# BluetoothAdapter2_0.net
KiCad netlist of a schematic drawn in Altium Designer
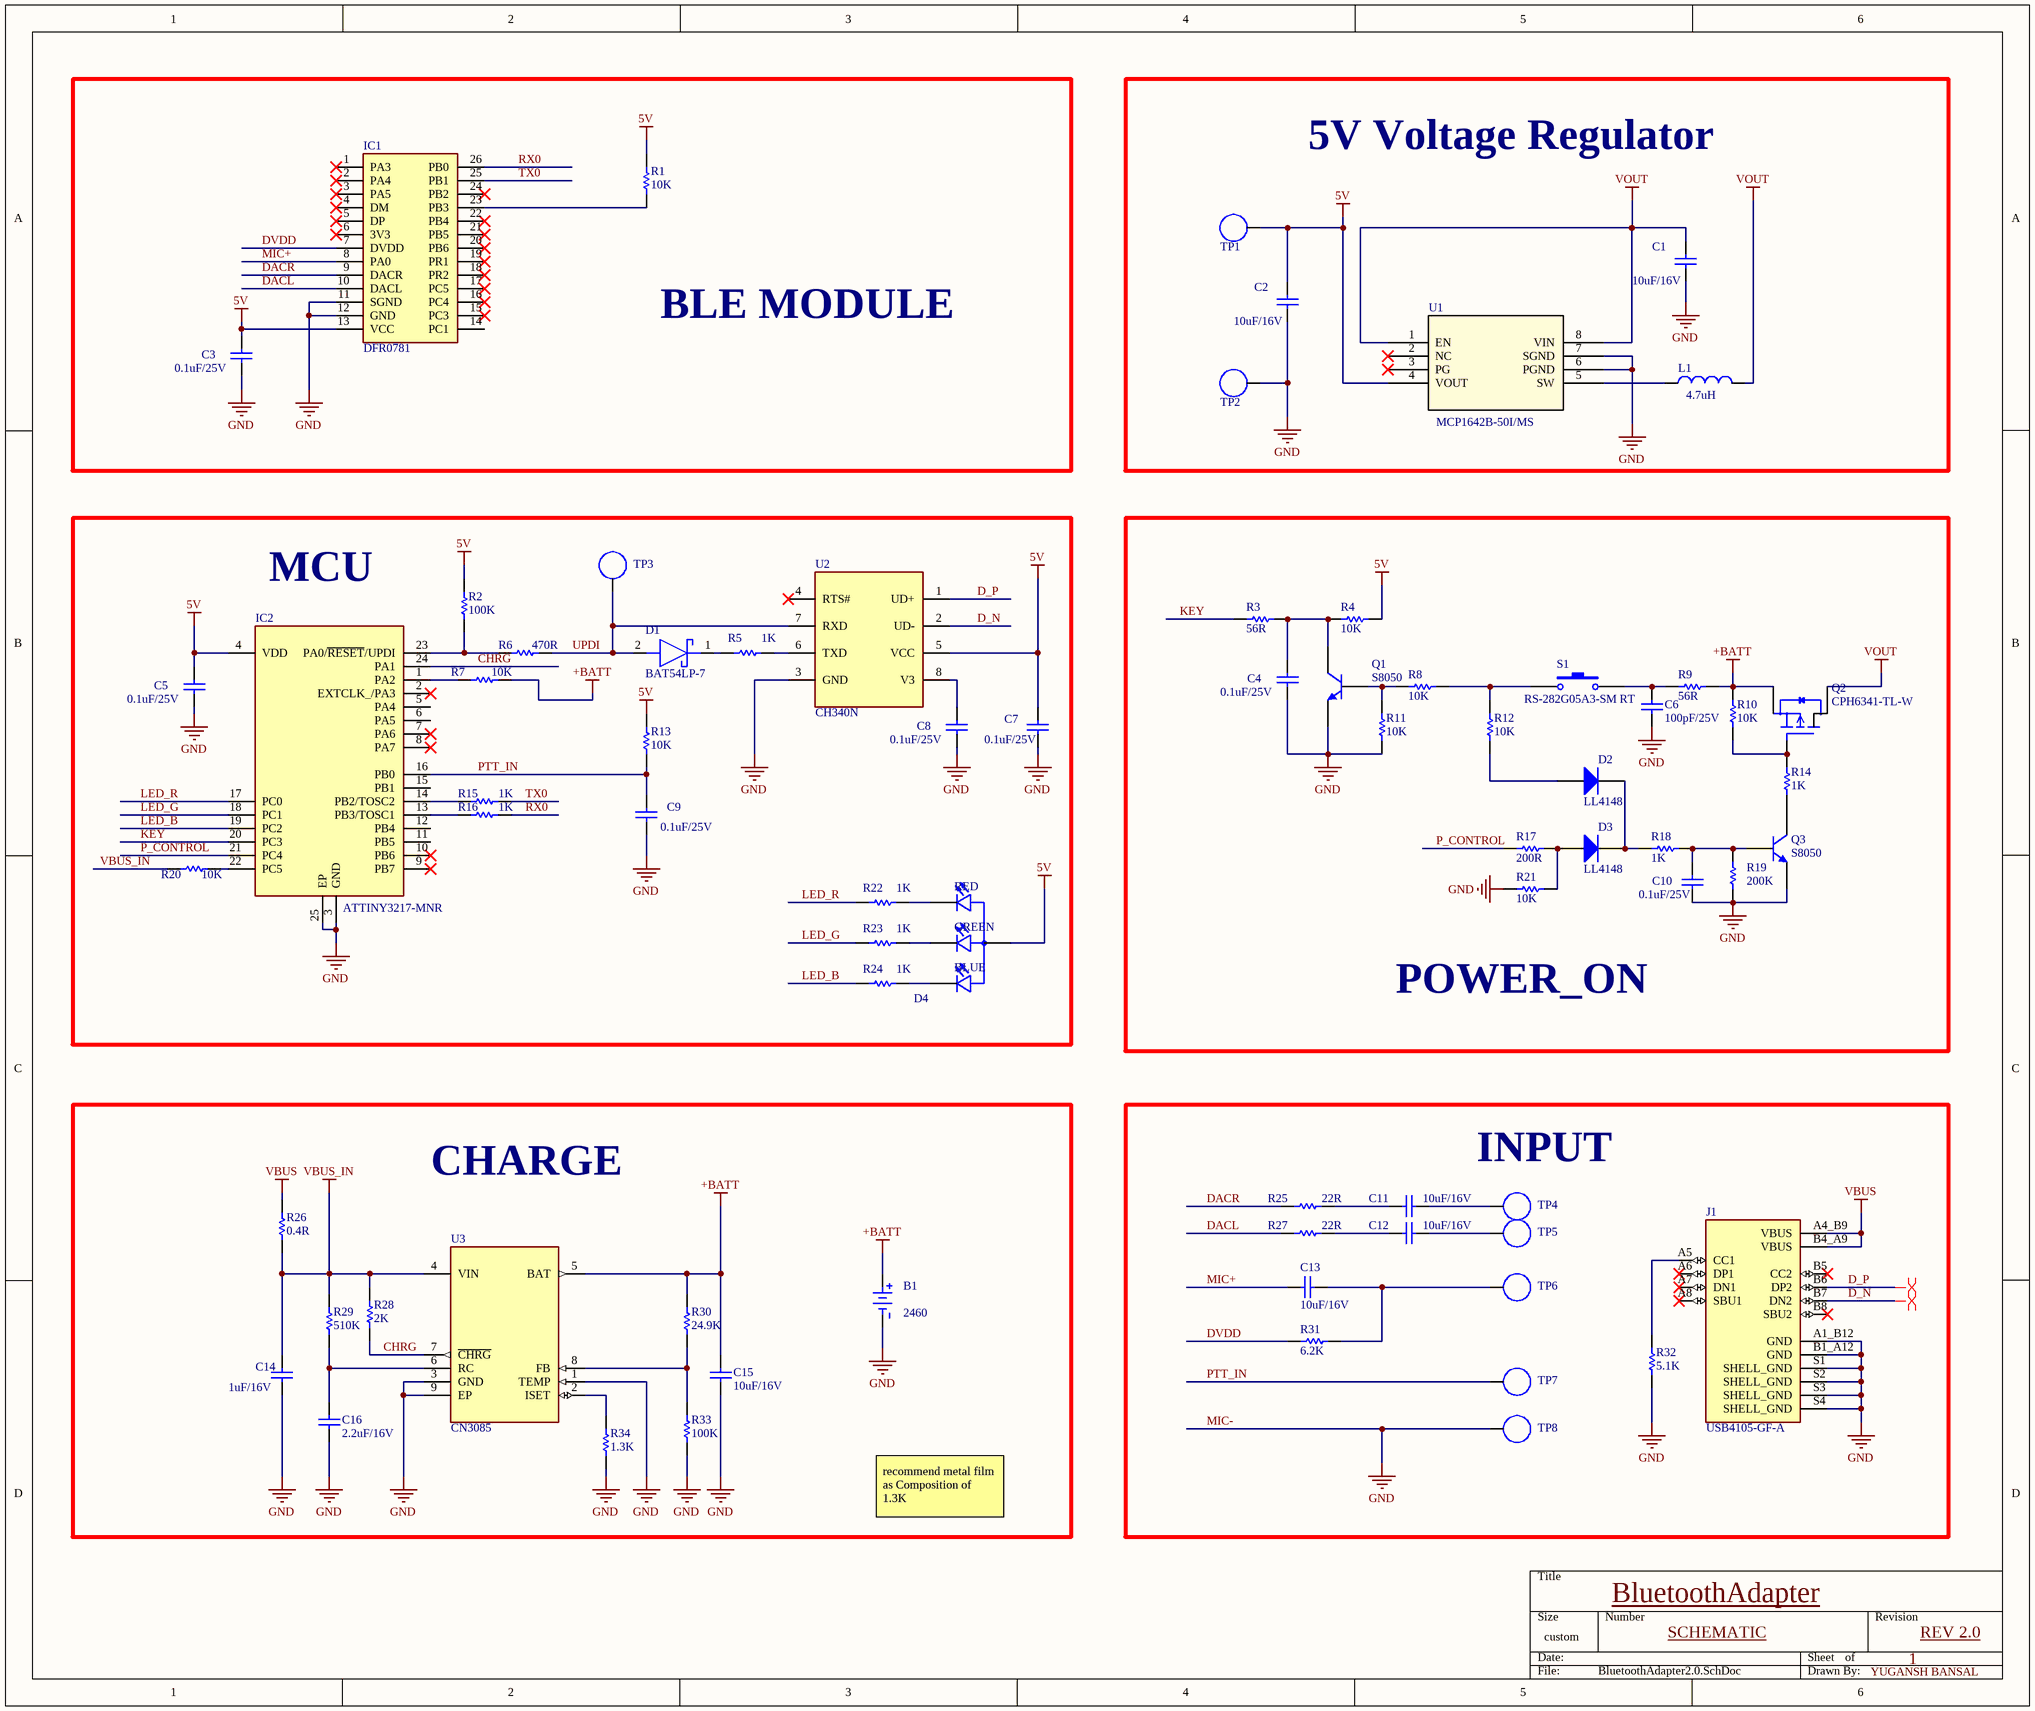
[diagram p0: BluetoothAdapter2.0.SchDoc]

(export (version "E")
  (design (tool "Eeschema 10.0.6"))
  (components
    (comp (ref "B1")
      (value "2460")
      (footprint "BluetoothAdapter:2460_KEY")
      (description "Battery Holder (Open) AA 1 Cell PC Pin")
      (fields
        (field (name "MANUFACTURER") "Keystone Electronics")
        (field (name "DIGI-KEY PART NUMBER") "36-2460-ND")
      )
      (libsource (lib "BluetoothAdapter") (part "2460"))
    )
    (comp (ref "C1")
      (value "10uF/16V")
      (footprint "BluetoothAdapter:C0603S")
      (description "10 µF ±20% 16V Ceramic Capacitor X5R 0603 (1608 Metric)")
      (fields
        (field (name "MANUFACTURER") "Murata Electronics")
        (field (name "DIGI-KEY PART NUMBER") "490-10729-6-ND")
      )
      (libsource (lib "myLib") (part "Cap"))
    )
    (comp (ref "C2")
      (value "10uF/16V")
      (footprint "BluetoothAdapter:C0603S")
      (description "10 µF ±20% 16V Ceramic Capacitor X5R 0603 (1608 Metric)")
      (fields
        (field (name "MANUFACTURER") "Murata Electronics")
        (field (name "DIGI-KEY PART NUMBER") "490-10729-6-ND")
      )
      (libsource (lib "myLib") (part "Cap"))
    )
    (comp (ref "C3")
      (value "0.1uF/25V")
      (footprint "BluetoothAdapter:C0603S")
      (description "0.1 µF ±10% 25V Ceramic Capacitor X7R 0603 (1608 Metric)")
      (fields
        (field (name "MANUFACTURER") "KEMET")
        (field (name "DIGI-KEY PART NUMBER") "399-C0603C104K3RAC7867TR-ND")
      )
      (libsource (lib "myLib") (part "Cap"))
    )
    (comp (ref "C4")
      (value "0.1uF/25V")
      (footprint "BluetoothAdapter:C0603S")
      (description "0.1 µF ±10% 25V Ceramic Capacitor X7R 0603 (1608 Metric)")
      (fields
        (field (name "MANUFACTURER") "KEMET")
        (field (name "DIGI-KEY PART NUMBER") "399-C0603C104K3RAC7867TR-ND")
      )
      (libsource (lib "myLib") (part "Cap"))
    )
    (comp (ref "C5")
      (value "0.1uF/25V")
      (footprint "BluetoothAdapter:C0603S")
      (description "0.1 µF ±10% 25V Ceramic Capacitor X7R 0603 (1608 Metric)")
      (fields
        (field (name "MANUFACTURER") "KEMET")
        (field (name "DIGI-KEY PART NUMBER") "399-C0603C104K3RAC7867TR-ND")
      )
      (libsource (lib "myLib") (part "Cap"))
    )
    (comp (ref "C6")
      (value "100pF/25V")
      (footprint "BluetoothAdapter:C0603S")
      (description "0.1 µF ±10% 25V Ceramic Capacitor X7R 0603 (1608 Metric)")
      (fields
        (field (name "MANUFACTURER") "KEMET")
        (field (name "DIGI-KEY PART NUMBER") "399-C0603C101K3RACAUTODKR-ND")
      )
      (libsource (lib "myLib") (part "Cap"))
    )
    (comp (ref "C7")
      (value "0.1uF/25V")
      (footprint "BluetoothAdapter:C0603S")
      (description "0.1 µF ±10% 25V Ceramic Capacitor X7R 0603 (1608 Metric)")
      (fields
        (field (name "MANUFACTURER") "KEMET")
        (field (name "DIGI-KEY PART NUMBER") "399-C0603C104K3RAC7867TR-ND")
      )
      (libsource (lib "myLib") (part "Cap"))
    )
    (comp (ref "C8")
      (value "0.1uF/25V")
      (footprint "BluetoothAdapter:C0603S")
      (description "0.1 µF ±10% 25V Ceramic Capacitor X7R 0603 (1608 Metric)")
      (fields
        (field (name "MANUFACTURER") "KEMET")
        (field (name "DIGI-KEY PART NUMBER") "399-C0603C104K3RAC7867TR-ND")
      )
      (libsource (lib "myLib") (part "Cap"))
    )
    (comp (ref "C9")
      (value "0.1uF/25V")
      (footprint "BluetoothAdapter:C0603S")
      (description "0.1 µF ±10% 25V Ceramic Capacitor X7R 0603 (1608 Metric)")
      (fields
        (field (name "MANUFACTURER") "KEMET")
        (field (name "DIGI-KEY PART NUMBER") "399-C0603C104K3RAC7867TR-ND")
      )
      (libsource (lib "myLib") (part "Cap"))
    )
    (comp (ref "C10")
      (value "0.1uF/25V")
      (footprint "BluetoothAdapter:C0603S")
      (description "0.1 µF ±10% 25V Ceramic Capacitor X7R 0603 (1608 Metric)")
      (fields
        (field (name "MANUFACTURER") "KEMET")
        (field (name "DIGI-KEY PART NUMBER") "399-C0603C104K3RAC7867TR-ND")
      )
      (libsource (lib "myLib") (part "Cap"))
    )
    (comp (ref "C11")
      (value "10uF/16V")
      (footprint "BluetoothAdapter:C0603S")
      (description "10 µF ±20% 16V Ceramic Capacitor X5R 0603 (1608 Metric)")
      (fields
        (field (name "MANUFACTURER") "Murata Electronics")
        (field (name "DIGI-KEY PART NUMBER") "490-10729-6-ND")
      )
      (libsource (lib "myLib") (part "Cap"))
    )
    (comp (ref "C12")
      (value "10uF/16V")
      (footprint "BluetoothAdapter:C0603S")
      (description "10 µF ±20% 16V Ceramic Capacitor X5R 0603 (1608 Metric)")
      (fields
        (field (name "MANUFACTURER") "Murata Electronics")
        (field (name "DIGI-KEY PART NUMBER") "490-10729-6-ND")
      )
      (libsource (lib "myLib") (part "Cap"))
    )
    (comp (ref "C13")
      (value "10uF/16V")
      (footprint "BluetoothAdapter:C0603S")
      (description "10 µF ±20% 16V Ceramic Capacitor X5R 0603 (1608 Metric)")
      (fields
        (field (name "MANUFACTURER") "Murata Electronics")
        (field (name "DIGI-KEY PART NUMBER") "490-10729-6-ND")
      )
      (libsource (lib "myLib") (part "Cap"))
    )
    (comp (ref "C14")
      (value "1uF/16V")
      (footprint "BluetoothAdapter:C0603S")
      (description "1 µF ±10% 16V Ceramic Capacitor X7R 0603 (1608 Metric)")
      (fields (field (name "MANUFACTURER") "YAGEO") (field (name "DIGI-KEY PART NUMBER") "311-1446-6-ND"))
      (libsource (lib "myLib") (part "Cap"))
    )
    (comp (ref "C15")
      (value "10uF/16V")
      (footprint "BluetoothAdapter:C0603S")
      (description "10 µF ±20% 16V Ceramic Capacitor X5R 0603 (1608 Metric)")
      (fields
        (field (name "MANUFACTURER") "Murata Electronics")
        (field (name "DIGI-KEY PART NUMBER") "490-10729-6-ND")
      )
      (libsource (lib "myLib") (part "Cap"))
    )
    (comp (ref "C16")
      (value "2.2uF/16V")
      (footprint "BluetoothAdapter:C0603S")
      (description "2.2 µF ±10% 16V Ceramic Capacitor X7R 0603 (1608 Metric)")
      (fields
        (field (name "MANUFACTURER") "Murata Electronics")
        (field (name "DIGI-KEY PART NUMBER") "490-GRM188Z71C225KE43DDKR-ND")
      )
      (libsource (lib "myLib") (part "Cap"))
    )
    (comp (ref "D1")
      (value "BAT54LP-7")
      (footprint "BluetoothAdapter:DESD3V3S1BL7B")
      (description "Diode 30 V 200mA Surface Mount X1-DFN1006-2")
      (fields
        (field (name "MANUFACTURER") "Diodes Inc.")
        (field (name "DIGI-KEY PART NUMBER") "BAT54LPDIDKR-ND")
      )
      (libsource (lib "BluetoothAdapter") (part "BAT54LP-7"))
    )
    (comp (ref "D2")
      (value "LL4148")
      (footprint "DIO_LL4148")
      (description "Diode Standard 100 V 200mA Surface Mount SOD-80")
      (fields (field (name "MANUFACTURER") "onsemi") (field (name "DIGI-KEY PART NUMBER") "LL4148FSCT-ND"))
      (libsource (lib "Miscellaneous Devices") (part "Diode"))
    )
    (comp (ref "D3")
      (value "LL4148")
      (footprint "DIO_LL4148")
      (description "Diode Standard 100 V 200mA Surface Mount SOD-80")
      (fields (field (name "MANUFACTURER") "onsemi") (field (name "DIGI-KEY PART NUMBER") "LL4148FSCT-ND"))
      (libsource (lib "Miscellaneous Devices") (part "Diode"))
    )
    (comp (ref "D4")
      (value "LED RGB MIXED WHITE ( 1.6(L)X1.6")
      (footprint "BluetoothAdapter:LED_B38G3RGB-10D0003H2U1930")
      (description "Red, Green, Blue (RGB) LED Indication - Discrete 2V Red, 3V Green, 3V Blue 0606 (1616 Metric)")
      (fields
        (field (name "MANUFACTURER") "Harvatek Corporation")
        (field (name "DIGI-KEY PART NUMBER") "3147-B38G3RGB-10D0003H2U1930DKR-ND")
      )
      (libsource (lib "BluetoothAdapter") (part "B38G3RGB-10D0003H2U1930"))
    )
    (comp (ref "IC1")
      (value "DFR0781")
      (footprint "BluetoothAdapter:DFR0781")
      (description "Bluetooth Bluetooth v5.0 Transceiver Module Antenna Not Included Surface Mount")
      (fields (field (name "MANUFACTURER") "DFRobot") (field (name "DIGI-KEY PART NUMBER") "1738-DFR0781-ND"))
      (libsource (lib "BluetoothAdapter") (part "DFR0781"))
    )
    (comp (ref "IC2")
      (value "ATTINY3217-MNR")
      (footprint "BluetoothAdapter:QFN50P400X400X90-25N-D")
      (fields
        (field (name "MANUFACTURER") "Microchip")
        (field (name "DIGI-KEY PART NUMBER") "ATTINY3217-MNRDKR-ND")
        (field (name "Comment") "IC MCU 8BIT 32KB FLASH 24VQFN")
      )
      (libsource (lib "BluetoothAdapter") (part "ATTINY3217-MNR"))
    )
    (comp (ref "J1")
      (value "USB4105-GF-A")
      (footprint "BluetoothAdapter:GCT_USB4105-GF-A")
      (fields
        (field (name "MANUFACTURER") "GCT")
        (field (name "DIGI-KEY PART NUMBER") "2073-USB4105-GF-ADKR-ND")
        (field (name "Comment") "CONN RCP USB2.0 TYP C 24P SMD RA")
      )
      (libsource (lib "BluetoothAdapter") (part "USB4105-GF-A"))
    )
    (comp (ref "L1")
      (value "4.7uH")
      (footprint "BluetoothAdapter:INDC2520X100N")
      (description "4.7 µH Shielded Multilayer Inductor 1.3 A 120mOhm 1008 (2520 Metric)")
      (fields
        (field (name "MANUFACTURER") "Abracon LLC")
        (field (name "DIGI-KEY PART NUMBER") "535-12797-6-ND")
      )
      (libsource (lib "Blueguard") (part "AIML-1008HC-4R7M-T"))
    )
    (comp (ref "Q1")
      (value "S8050")
      (footprint "BluetoothAdapter:SOT23-3D")
      (description "Bipolar (BJT) Transistor NPN 25 V 500 mA 150MHz 300 mW Surface Mount SOT-23")
      (fields (field (name "MANUFACTURER") "MDD") (field (name "DIGI-KEY PART NUMBER") "3372-S8050TR-ND"))
      (libsource (lib "BluetoothAdapter") (part "S8050"))
    )
    (comp (ref "Q2")
      (value "CPH6341-TL-W")
      (footprint "BluetoothAdapter:SOT95P285X140-6N")
      (description "P-Channel 30 V 5A (Ta) 1.6W (Ta) Surface Mount 6-CPH")
      (fields
        (field (name "MANUFACTURER") "onsemi")
        (field (name "DIGI-KEY PART NUMBER") "CPH6341-TL-WOSDKR-ND")
      )
      (libsource (lib "BluetoothAdapter") (part "CPH6341-TL-W"))
    )
    (comp (ref "Q3")
      (value "S8050")
      (footprint "BluetoothAdapter:SOT23-3D")
      (description "Bipolar (BJT) Transistor NPN 25 V 500 mA 150MHz 300 mW Surface Mount SOT-23")
      (fields (field (name "MANUFACTURER") "MDD") (field (name "DIGI-KEY PART NUMBER") "3372-S8050TR-ND"))
      (libsource (lib "BluetoothAdapter") (part "S8050"))
    )
    (comp (ref "R1")
      (value "10K")
      (footprint "BluetoothAdapter:R0603S")
      (description "10 kOhms ±1% 0.1W, 1/10W Chip Resistor 0603 (1608 Metric) Moisture Resistant Thick Film")
      (fields (field (name "MANUFACTURER") "YAGEO") (field (name "DIGI-KEY PART NUMBER") "311-10.0KHRCT-ND"))
      (libsource (lib "dif") (part "R0603"))
    )
    (comp (ref "R2")
      (value "100K")
      (footprint "BluetoothAdapter:R0603S")
      (description "100 kOhms ±1% 0.1W, 1/10W Chip Resistor 0603 (1608 Metric) Moisture Resistant Thick Film")
      (fields (field (name "MANUFACTURER") "YAGEO") (field (name "DIGI-KEY PART NUMBER") "311-100KHRDKR-ND"))
      (libsource (lib "dif") (part "R0603"))
    )
    (comp (ref "R3")
      (value "56R")
      (footprint "BluetoothAdapter:R0603S")
      (description "1 kOhms ±1% 0.1W, 1/10W Chip Resistor 0603 (1608 Metric) Moisture Resistant Thick Film")
      (fields (field (name "MANUFACTURER") "YAGEO") (field (name "DIGI-KEY PART NUMBER") "311-56.0HRDKR-ND"))
      (libsource (lib "dif") (part "R0603"))
    )
    (comp (ref "R4")
      (value "10K")
      (footprint "BluetoothAdapter:R0603S")
      (description "10 kOhms ±1% 0.1W, 1/10W Chip Resistor 0603 (1608 Metric) Moisture Resistant Thick Film")
      (fields (field (name "MANUFACTURER") "YAGEO") (field (name "DIGI-KEY PART NUMBER") "311-10.0KHRCT-ND"))
      (libsource (lib "dif") (part "R0603"))
    )
    (comp (ref "R5")
      (value "1K")
      (footprint "BluetoothAdapter:R0603S")
      (description "1 kOhms ±1% 0.1W, 1/10W Chip Resistor 0603 (1608 Metric) Moisture Resistant Thick Film")
      (fields (field (name "MANUFACTURER") "YAGEO") (field (name "DIGI-KEY PART NUMBER") "311-1.00KHRTR-ND"))
      (libsource (lib "dif") (part "R0603"))
    )
    (comp (ref "R6")
      (value "470R")
      (footprint "BluetoothAdapter:R0603S")
      (description "470 Ohms ±1% 0.1W, 1/10W Chip Resistor 0603 (1608 Metric) Moisture Resistant Thick Film")
      (fields (field (name "MANUFACTURER") "YAGEO") (field (name "DIGI-KEY PART NUMBER") "311-470HRDKR-ND"))
      (libsource (lib "dif") (part "R0603"))
    )
    (comp (ref "R7")
      (value "10K")
      (footprint "BluetoothAdapter:R0603S")
      (description "10 kOhms ±1% 0.1W, 1/10W Chip Resistor 0603 (1608 Metric) Moisture Resistant Thick Film")
      (fields (field (name "MANUFACTURER") "YAGEO") (field (name "DIGI-KEY PART NUMBER") "311-10.0KHRCT-ND"))
      (libsource (lib "dif") (part "R0603"))
    )
    (comp (ref "R8")
      (value "10K")
      (footprint "BluetoothAdapter:R0603S")
      (description "10 kOhms ±1% 0.1W, 1/10W Chip Resistor 0603 (1608 Metric) Moisture Resistant Thick Film")
      (fields (field (name "MANUFACTURER") "YAGEO") (field (name "DIGI-KEY PART NUMBER") "311-10.0KHRCT-ND"))
      (libsource (lib "dif") (part "R0603"))
    )
    (comp (ref "R9")
      (value "56R")
      (footprint "BluetoothAdapter:R0603S")
      (description "1 kOhms ±1% 0.1W, 1/10W Chip Resistor 0603 (1608 Metric) Moisture Resistant Thick Film")
      (fields (field (name "MANUFACTURER") "YAGEO") (field (name "DIGI-KEY PART NUMBER") "311-56.0HRDKR-ND"))
      (libsource (lib "dif") (part "R0603"))
    )
    (comp (ref "R10")
      (value "10K")
      (footprint "BluetoothAdapter:R0603S")
      (description "10 kOhms ±1% 0.1W, 1/10W Chip Resistor 0603 (1608 Metric) Moisture Resistant Thick Film")
      (fields (field (name "MANUFACTURER") "YAGEO") (field (name "DIGI-KEY PART NUMBER") "311-10.0KHRCT-ND"))
      (libsource (lib "dif") (part "R0603"))
    )
    (comp (ref "R11")
      (value "10K")
      (footprint "BluetoothAdapter:R0603S")
      (description "10 kOhms ±1% 0.1W, 1/10W Chip Resistor 0603 (1608 Metric) Moisture Resistant Thick Film")
      (fields (field (name "MANUFACTURER") "YAGEO") (field (name "DIGI-KEY PART NUMBER") "311-10.0KHRCT-ND"))
      (libsource (lib "dif") (part "R0603"))
    )
    (comp (ref "R12")
      (value "10K")
      (footprint "BluetoothAdapter:R0603S")
      (description "10 kOhms ±1% 0.1W, 1/10W Chip Resistor 0603 (1608 Metric) Moisture Resistant Thick Film")
      (fields (field (name "MANUFACTURER") "YAGEO") (field (name "DIGI-KEY PART NUMBER") "311-10.0KHRCT-ND"))
      (libsource (lib "dif") (part "R0603"))
    )
    (comp (ref "R13")
      (value "10K")
      (footprint "BluetoothAdapter:R0603S")
      (description "10 kOhms ±1% 0.1W, 1/10W Chip Resistor 0603 (1608 Metric) Moisture Resistant Thick Film")
      (fields (field (name "MANUFACTURER") "YAGEO") (field (name "DIGI-KEY PART NUMBER") "311-10.0KHRCT-ND"))
      (libsource (lib "dif") (part "R0603"))
    )
    (comp (ref "R14")
      (value "1K")
      (footprint "BluetoothAdapter:R0603S")
      (description "1 kOhms ±1% 0.1W, 1/10W Chip Resistor 0603 (1608 Metric) Moisture Resistant Thick Film")
      (fields (field (name "MANUFACTURER") "YAGEO") (field (name "DIGI-KEY PART NUMBER") "311-1.00KHRTR-ND"))
      (libsource (lib "dif") (part "R0603"))
    )
    (comp (ref "R15")
      (value "1K")
      (footprint "BluetoothAdapter:R0603S")
      (description "1 kOhms ±1% 0.1W, 1/10W Chip Resistor 0603 (1608 Metric) Moisture Resistant Thick Film")
      (fields (field (name "MANUFACTURER") "YAGEO") (field (name "DIGI-KEY PART NUMBER") "311-1.00KHRTR-ND"))
      (libsource (lib "dif") (part "R0603"))
    )
    (comp (ref "R16")
      (value "1K")
      (footprint "BluetoothAdapter:R0603S")
      (description "1 kOhms ±1% 0.1W, 1/10W Chip Resistor 0603 (1608 Metric) Moisture Resistant Thick Film")
      (fields (field (name "MANUFACTURER") "YAGEO") (field (name "DIGI-KEY PART NUMBER") "311-1.00KHRTR-ND"))
      (libsource (lib "dif") (part "R0603"))
    )
    (comp (ref "R17")
      (value "200R")
      (footprint "BluetoothAdapter:R0603S")
      (description "10 kOhms ±1% 0.1W, 1/10W Chip Resistor 0603 (1608 Metric) Moisture Resistant Thick Film")
      (fields (field (name "MANUFACTURER") "YAGEO") (field (name "DIGI-KEY PART NUMBER") "311-200HRDKR-ND"))
      (libsource (lib "dif") (part "R0603"))
    )
    (comp (ref "R18")
      (value "1K")
      (footprint "BluetoothAdapter:R0603S")
      (description "1 kOhms ±1% 0.1W, 1/10W Chip Resistor 0603 (1608 Metric) Moisture Resistant Thick Film")
      (fields (field (name "MANUFACTURER") "YAGEO") (field (name "DIGI-KEY PART NUMBER") "311-1.00KHRTR-ND"))
      (libsource (lib "dif") (part "R0603"))
    )
    (comp (ref "R19")
      (value "200K")
      (footprint "BluetoothAdapter:R0603S")
      (description "100 kOhms ±1% 0.1W, 1/10W Chip Resistor 0603 (1608 Metric) Moisture Resistant Thick Film")
      (fields
        (field (name "MANUFACTURER") "YAGEO")
        (field (name "DIGI-KEY PART NUMBER") "13-RC0603FR-10200KLDKR-ND")
      )
      (libsource (lib "dif") (part "R0603"))
    )
    (comp (ref "R20")
      (value "10K")
      (footprint "BluetoothAdapter:R0603S")
      (description "10 kOhms ±1% 0.1W, 1/10W Chip Resistor 0603 (1608 Metric) Moisture Resistant Thick Film")
      (fields (field (name "MANUFACTURER") "YAGEO") (field (name "DIGI-KEY PART NUMBER") "311-10.0KHRCT-ND"))
      (libsource (lib "dif") (part "R0603"))
    )
    (comp (ref "R21")
      (value "10K")
      (footprint "BluetoothAdapter:R0603S")
      (description "10 kOhms ±1% 0.1W, 1/10W Chip Resistor 0603 (1608 Metric) Moisture Resistant Thick Film")
      (fields (field (name "MANUFACTURER") "YAGEO") (field (name "DIGI-KEY PART NUMBER") "311-10.0KHRCT-ND"))
      (libsource (lib "dif") (part "R0603"))
    )
    (comp (ref "R22")
      (value "1K")
      (footprint "BluetoothAdapter:R0603S")
      (description "1 kOhms ±1% 0.1W, 1/10W Chip Resistor 0603 (1608 Metric) Moisture Resistant Thick Film")
      (fields (field (name "MANUFACTURER") "YAGEO") (field (name "DIGI-KEY PART NUMBER") "311-1.00KHRTR-ND"))
      (libsource (lib "dif") (part "R0603"))
    )
    (comp (ref "R23")
      (value "1K")
      (footprint "BluetoothAdapter:R0603S")
      (description "1 kOhms ±1% 0.1W, 1/10W Chip Resistor 0603 (1608 Metric) Moisture Resistant Thick Film")
      (fields (field (name "MANUFACTURER") "YAGEO") (field (name "DIGI-KEY PART NUMBER") "311-1.00KHRTR-ND"))
      (libsource (lib "dif") (part "R0603"))
    )
    (comp (ref "R24")
      (value "1K")
      (footprint "BluetoothAdapter:R0603S")
      (description "1 kOhms ±1% 0.1W, 1/10W Chip Resistor 0603 (1608 Metric) Moisture Resistant Thick Film")
      (fields (field (name "MANUFACTURER") "YAGEO") (field (name "DIGI-KEY PART NUMBER") "311-1.00KHRTR-ND"))
      (libsource (lib "dif") (part "R0603"))
    )
    (comp (ref "R25")
      (value "22R")
      (footprint "BluetoothAdapter:R0603S")
      (description "22 Ohms ±5% 0.1W, 1/10W Chip Resistor 0603 (1608 Metric) Moisture Resistant Thick Film")
      (fields (field (name "MANUFACTURER") "YAGEO") (field (name "DIGI-KEY PART NUMBER") "311-22GRDKR-ND"))
      (libsource (lib "dif") (part "R0603"))
    )
    (comp (ref "R26")
      (value "0.4R")
      (footprint "BluetoothAdapter:R1206S")
      (fields
        (field (name "MANUFACTURER") "YAGEO")
        (field (name "DIGI-KEY PART NUMBER") "311-.4LWDKR-ND")
        (field (name "Comment") "RES 0.4 OHM 1% 1/4W 1206")
      )
      (libsource (lib "dif") (part "R0603"))
    )
    (comp (ref "R27")
      (value "22R")
      (footprint "BluetoothAdapter:R0603S")
      (description "22 Ohms ±5% 0.1W, 1/10W Chip Resistor 0603 (1608 Metric) Moisture Resistant Thick Film")
      (fields (field (name "MANUFACTURER") "YAGEO") (field (name "DIGI-KEY PART NUMBER") "311-22GRDKR-ND"))
      (libsource (lib "dif") (part "R0603"))
    )
    (comp (ref "R28")
      (value "2K")
      (footprint "BluetoothAdapter:R0603S")
      (description "2 kOhms ±1% 0.1W, 1/10W Chip Resistor 0603 (1608 Metric) Moisture Resistant Thick Film")
      (fields (field (name "MANUFACTURER") "YAGEO") (field (name "DIGI-KEY PART NUMBER") "311-2.00KHRDKR-ND"))
      (libsource (lib "dif") (part "R0603"))
    )
    (comp (ref "R29")
      (value "510K")
      (footprint "BluetoothAdapter:R0603S")
      (description "510 kOhms ±1% 0.1W, 1/10W Chip Resistor 0603 (1608 Metric) Moisture Resistant Thick Film")
      (fields (field (name "MANUFACTURER") "YAGEO") (field (name "DIGI-KEY PART NUMBER") "311-510KHRDKR-ND"))
      (libsource (lib "dif") (part "R0603"))
    )
    (comp (ref "R30")
      (value "24.9K")
      (footprint "BluetoothAdapter:R0603S")
      (description "24.9 kOhms ±1% 0.1W, 1/10W Chip Resistor 0603 (1608 Metric) Moisture Resistant Thick Film")
      (fields (field (name "MANUFACTURER") "YAGEO") (field (name "DIGI-KEY PART NUMBER") "311-24.9KHRDKR-ND"))
      (libsource (lib "dif") (part "R0603"))
    )
    (comp (ref "R31")
      (value "6.2K")
      (footprint "BluetoothAdapter:R0603S")
      (description "6.2 kOhms ±1% 0.1W, 1/10W Chip Resistor 0603 (1608 Metric) Moisture Resistant Thick Film")
      (fields (field (name "MANUFACTURER") "YAGEO") (field (name "DIGI-KEY PART NUMBER") "311-6.20KHRDKR-ND"))
      (libsource (lib "dif") (part "R0603"))
    )
    (comp (ref "R32")
      (value "5.1K")
      (footprint "BluetoothAdapter:R0603S")
      (description "5.1kOhms ±1% 0.1W, 1/10W Chip Resistor 0603 (1608 Metric) Moisture Resistant Thick Film")
      (fields (field (name "MANUFACTURER") "YAGEO") (field (name "DIGI-KEY PART NUMBER") "311-5.10KHRDKR-ND"))
      (libsource (lib "dif") (part "R0603"))
    )
    (comp (ref "R33")
      (value "100K")
      (footprint "BluetoothAdapter:R0603S")
      (description "100 kOhms ±1% 0.1W, 1/10W Chip Resistor 0603 (1608 Metric) Moisture Resistant Thick Film")
      (fields (field (name "MANUFACTURER") "YAGEO") (field (name "DIGI-KEY PART NUMBER") "311-100KHRDKR-ND"))
      (libsource (lib "dif") (part "R0603"))
    )
    (comp (ref "R34")
      (value "1.3K")
      (footprint "BluetoothAdapter:R0603S")
      (fields
        (field (name "MANUFACTURER") "KOA Speer Electronics, Inc.")
        (field (name "DIGI-KEY PART NUMBER") "2019-RN73H1JTTD1301F100DKR-ND")
        (field (name "Comment") "RES 1.3K OHM 1% 1/10W 0603")
      )
      (libsource (lib "dif") (part "R0603"))
    )
    (comp (ref "S1")
      (value "RS-282G05A3-SM RT")
      (footprint "BluetoothAdapter:RS282G05A3SMRT")
      (description "Tactile Switch SPST-NO Top Actuated Surface Mount")
      (fields
        (field (name "MANUFACTURER") "C & K COMPONENTS")
        (field (name "DIGI-KEY PART NUMBER") "CKN10384DKR-ND")
      )
      (libsource (lib "BluetoothAdapter") (part "RS282G05A3SMRT"))
    )
    (comp (ref "TP1")
      (value "TP")
      (footprint "BluetoothAdapter:TP")
      (libsource (lib "BluetoothAdapter") (part "TP"))
    )
    (comp (ref "TP2")
      (value "TP")
      (footprint "BluetoothAdapter:TP")
      (libsource (lib "BluetoothAdapter") (part "TP"))
    )
    (comp (ref "TP3")
      (value "TP")
      (footprint "BluetoothAdapter:TP")
      (libsource (lib "BluetoothAdapter") (part "TP"))
    )
    (comp (ref "TP4")
      (value "TP")
      (footprint "BluetoothAdapter:TP")
      (libsource (lib "BluetoothAdapter") (part "TP"))
    )
    (comp (ref "TP5")
      (value "TP")
      (footprint "BluetoothAdapter:TP")
      (libsource (lib "BluetoothAdapter") (part "TP"))
    )
    (comp (ref "TP6")
      (value "TP")
      (footprint "BluetoothAdapter:TP")
      (libsource (lib "BluetoothAdapter") (part "TP"))
    )
    (comp (ref "TP7")
      (value "TP")
      (footprint "BluetoothAdapter:TP")
      (libsource (lib "BluetoothAdapter") (part "TP"))
    )
    (comp (ref "TP8")
      (value "TP")
      (footprint "BluetoothAdapter:TP")
      (libsource (lib "BluetoothAdapter") (part "TP"))
    )
    (comp (ref "U1")
      (value "MCP1642B-50I/MS")
      (footprint "BluetoothAdapter:MCP1642B-50I/MS")
      (fields
        (field (name "MANUFACTURER") "Microchip Technology")
        (field (name "DIGI-KEY PART NUMBER") "MCP1642B-50I/MS-ND")
        (field (name "Comment") "IC REG BOOST 5V 800MA 8MSOP")
      )
      (libsource (lib "Blueguard") (part "MCP1642B-50I/MS"))
    )
    (comp (ref "U2")
      (value "CH340N")
      (footprint "BluetoothAdapter:SOIC127P602X173-8N")
      (description "IC USB TO UART BRIDGE SOP-8")
      (fields
        (field (name "MANUFACTURER") "WCH(Jiangsu Qin Heng)")
        (field (name "DIGI-KEY PART NUMBER") "C506813")
      )
      (libsource (lib "BluetoothAdapter") (part "CH340N"))
    )
    (comp (ref "U3")
      (value "CN3085")
      (footprint "BluetoothAdapter:SOP-8_L4.9-W3.9-P1.27-LS6.0-BL-EP")
      (description "SOP-8-EP Battery Management ICs ROHS")
      (fields
        (field (name "MANUFACTURER") "ShangHai Consonance Elec")
        (field (name "DIGI-KEY PART NUMBER") "C93054")
      )
      (libsource (lib "BluetoothAdapter") (part "CN3085"))
    )
  )
  (nets
    (net (code "1") (name "+BATT") (class "Default")
      (node (ref "B1") (pin "1") (pinfunction "+_1") (pintype "passive"))
      (node (ref "C15") (pin "2") (pinfunction "2_2") (pintype "passive"))
      (node (ref "Q2") (pin "4") (pinfunction "S_4") (pintype "passive"))
      (node (ref "R10") (pin "1") (pinfunction "1_1") (pintype "passive"))
      (node (ref "R30") (pin "1") (pinfunction "1_1") (pintype "passive"))
      (node (ref "R7") (pin "2") (pinfunction "2_2") (pintype "passive"))
      (node (ref "R9") (pin "2") (pinfunction "2_2") (pintype "passive"))
      (node (ref "U3") (pin "5") (pinfunction "BAT_5") (pintype "output"))
    )
    (net (code "2") (name "/CHRG") (class "Default")
      (node (ref "IC2") (pin "24") (pinfunction "PA1_24") (pintype "passive"))
      (node (ref "R28") (pin "2") (pinfunction "2_2") (pintype "passive"))
      (node (ref "U3") (pin "7") (pinfunction "~{CHRG}_7") (pintype "output"))
    )
    (net (code "3") (name "/DACL") (class "Default")
      (node (ref "IC1") (pin "10") (pinfunction "DACL_10") (pintype "passive"))
      (node (ref "R27") (pin "1") (pinfunction "1_1") (pintype "passive"))
    )
    (net (code "4") (name "/DACR") (class "Default")
      (node (ref "IC1") (pin "9") (pinfunction "DACR_9") (pintype "passive"))
      (node (ref "R25") (pin "1") (pinfunction "1_1") (pintype "passive"))
    )
    (net (code "5") (name "/DVDD") (class "Default")
      (node (ref "IC1") (pin "7") (pinfunction "DVDD_7") (pintype "passive"))
      (node (ref "R31") (pin "1") (pinfunction "1_1") (pintype "passive"))
    )
    (net (code "6") (name "/D_N") (class "Default")
      (node (ref "J1") (pin "B7") (pinfunction "DN2_B7") (pintype "bidirectional"))
      (node (ref "U2") (pin "2") (pinfunction "UD-_2") (pintype "passive"))
    )
    (net (code "7") (name "/D_P") (class "Default")
      (node (ref "J1") (pin "B6") (pinfunction "DP2_B6") (pintype "bidirectional"))
      (node (ref "U2") (pin "1") (pinfunction "UD+_1") (pintype "passive"))
    )
    (net (code "8") (name "/KEY") (class "Default")
      (node (ref "IC2") (pin "20") (pinfunction "PC3_20") (pintype "passive"))
      (node (ref "R3") (pin "1") (pinfunction "1_1") (pintype "passive"))
    )
    (net (code "9") (name "/LED_B") (class "Default")
      (node (ref "IC2") (pin "19") (pinfunction "PC2_19") (pintype "passive"))
      (node (ref "R24") (pin "1") (pinfunction "1_1") (pintype "passive"))
    )
    (net (code "10") (name "/LED_G") (class "Default")
      (node (ref "IC2") (pin "18") (pinfunction "PC1_18") (pintype "passive"))
      (node (ref "R23") (pin "1") (pinfunction "1_1") (pintype "passive"))
    )
    (net (code "11") (name "/LED_R") (class "Default")
      (node (ref "IC2") (pin "17") (pinfunction "PC0_17") (pintype "passive"))
      (node (ref "R22") (pin "1") (pinfunction "1_1") (pintype "passive"))
    )
    (net (code "12") (name "/MIC+") (class "Default")
      (node (ref "C13") (pin "2") (pinfunction "2_2") (pintype "passive"))
      (node (ref "IC1") (pin "8") (pinfunction "PA0_8") (pintype "passive"))
    )
    (net (code "13") (name "/PTT_IN") (class "Default")
      (node (ref "C9") (pin "1") (pinfunction "1_1") (pintype "passive"))
      (node (ref "IC2") (pin "16") (pinfunction "PB0_16") (pintype "passive"))
      (node (ref "R13") (pin "2") (pinfunction "2_2") (pintype "passive"))
      (node (ref "TP7") (pin "1") (pinfunction "1_1") (pintype "passive"))
    )
    (net (code "14") (name "/P_CONTROL") (class "Default")
      (node (ref "IC2") (pin "21") (pinfunction "PC4_21") (pintype "passive"))
      (node (ref "R17") (pin "1") (pinfunction "1_1") (pintype "passive"))
    )
    (net (code "15") (name "/RX0") (class "Default")
      (node (ref "IC1") (pin "26") (pinfunction "PB0_26") (pintype "passive"))
      (node (ref "R16") (pin "2") (pinfunction "2_2") (pintype "passive"))
    )
    (net (code "16") (name "/TX0") (class "Default")
      (node (ref "IC1") (pin "25") (pinfunction "PB1_25") (pintype "passive"))
      (node (ref "R15") (pin "2") (pinfunction "2_2") (pintype "passive"))
    )
    (net (code "17") (name "/UPDI") (class "Default")
      (node (ref "D1") (pin "2") (pinfunction "A_2") (pintype "passive"))
      (node (ref "R6") (pin "1") (pinfunction "1_1") (pintype "passive"))
      (node (ref "TP3") (pin "1") (pinfunction "1_1") (pintype "passive"))
      (node (ref "U2") (pin "7") (pinfunction "RXD_7") (pintype "power_in"))
    )
    (net (code "18") (name "5V") (class "Default")
      (node (ref "C2") (pin "2") (pinfunction "2_2") (pintype "passive"))
      (node (ref "C3") (pin "1") (pinfunction "1_1") (pintype "passive"))
      (node (ref "C5") (pin "1") (pinfunction "1_1") (pintype "passive"))
      (node (ref "C7") (pin "1") (pinfunction "1_1") (pintype "passive"))
      (node (ref "D4") (pin "3") (pinfunction "A_3") (pintype "passive"))
      (node (ref "IC1") (pin "13") (pinfunction "VCC_13") (pintype "passive"))
      (node (ref "IC2") (pin "4") (pinfunction "VDD_4") (pintype "passive"))
      (node (ref "R1") (pin "2") (pinfunction "2_2") (pintype "passive"))
      (node (ref "R13") (pin "1") (pinfunction "1_1") (pintype "passive"))
      (node (ref "R2") (pin "1") (pinfunction "1_1") (pintype "passive"))
      (node (ref "R4") (pin "1") (pinfunction "1_1") (pintype "passive"))
      (node (ref "TP1") (pin "1") (pinfunction "1_1") (pintype "passive"))
      (node (ref "U1") (pin "4") (pinfunction "VOUT_4") (pintype "passive"))
      (node (ref "U2") (pin "5") (pinfunction "VCC_5") (pintype "passive"))
    )
    (net (code "19") (name "GND") (class "Default")
      (node (ref "B1") (pin "2") (pinfunction "-_2") (pintype "passive"))
      (node (ref "C1") (pin "1") (pinfunction "1_1") (pintype "passive"))
      (node (ref "C10") (pin "2") (pinfunction "2_2") (pintype "passive"))
      (node (ref "C14") (pin "1") (pinfunction "1_1") (pintype "passive"))
      (node (ref "C15") (pin "1") (pinfunction "1_1") (pintype "passive"))
      (node (ref "C16") (pin "1") (pinfunction "1_1") (pintype "passive"))
      (node (ref "C2") (pin "1") (pinfunction "1_1") (pintype "passive"))
      (node (ref "C3") (pin "2") (pinfunction "2_2") (pintype "passive"))
      (node (ref "C4") (pin "2") (pinfunction "2_2") (pintype "passive"))
      (node (ref "C5") (pin "2") (pinfunction "2_2") (pintype "passive"))
      (node (ref "C6") (pin "1") (pinfunction "1_1") (pintype "passive"))
      (node (ref "C7") (pin "2") (pinfunction "2_2") (pintype "passive"))
      (node (ref "C8") (pin "2") (pinfunction "2_2") (pintype "passive"))
      (node (ref "C9") (pin "2") (pinfunction "2_2") (pintype "passive"))
      (node (ref "IC1") (pin "11") (pinfunction "SGND_11") (pintype "passive"))
      (node (ref "IC1") (pin "12") (pinfunction "GND_12") (pintype "passive"))
      (node (ref "IC2") (pin "25") (pinfunction "EP_25") (pintype "passive"))
      (node (ref "IC2") (pin "3") (pinfunction "GND_3") (pintype "passive"))
      (node (ref "J1") (pin "A1_B12") (pinfunction "GND_A1_B12") (pintype "power_in"))
      (node (ref "J1") (pin "B1_A12") (pinfunction "GND_B1_A12") (pintype "power_in"))
      (node (ref "J1") (pin "S1") (pinfunction "SHELL_GND_S1") (pintype "power_in"))
      (node (ref "J1") (pin "S2") (pinfunction "SHELL_GND_S2") (pintype "power_in"))
      (node (ref "J1") (pin "S3") (pinfunction "SHELL_GND_S3") (pintype "power_in"))
      (node (ref "J1") (pin "S4") (pinfunction "SHELL_GND_S4") (pintype "power_in"))
      (node (ref "Q1") (pin "3") (pinfunction "E_3") (pintype "passive"))
      (node (ref "Q3") (pin "3") (pinfunction "E_3") (pintype "passive"))
      (node (ref "R11") (pin "2") (pinfunction "2_2") (pintype "passive"))
      (node (ref "R19") (pin "1") (pinfunction "1_1") (pintype "passive"))
      (node (ref "R21") (pin "1") (pinfunction "1_1") (pintype "passive"))
      (node (ref "R32") (pin "2") (pinfunction "2_2") (pintype "passive"))
      (node (ref "R33") (pin "2") (pinfunction "2_2") (pintype "passive"))
      (node (ref "R34") (pin "2") (pinfunction "2_2") (pintype "passive"))
      (node (ref "TP2") (pin "1") (pinfunction "1_1") (pintype "passive"))
      (node (ref "TP8") (pin "1") (pinfunction "1_1") (pintype "passive"))
      (node (ref "U1") (pin "6") (pinfunction "PGND_6") (pintype "passive"))
      (node (ref "U1") (pin "7") (pinfunction "SGND_7") (pintype "passive"))
      (node (ref "U2") (pin "3") (pinfunction "GND_3") (pintype "passive"))
      (node (ref "U3") (pin "1") (pinfunction "TEMP_1") (pintype "input"))
      (node (ref "U3") (pin "3") (pinfunction "GND_3") (pintype "power_in"))
      (node (ref "U3") (pin "9") (pinfunction "EP_9") (pintype "passive"))
    )
    (net (code "20") (name "Net-(C6-Pad2)") (class "Default")
      (node (ref "C6") (pin "2") (pinfunction "2_2") (pintype "passive"))
      (node (ref "R9") (pin "1") (pinfunction "1_1") (pintype "passive"))
      (node (ref "S1") (pin "2") (pinfunction "2_2") (pintype "passive"))
    )
    (net (code "21") (name "Net-(C11-Pad1)") (class "Default")
      (node (ref "C11") (pin "1") (pinfunction "1_1") (pintype "passive"))
      (node (ref "TP4") (pin "1") (pinfunction "1_1") (pintype "passive"))
    )
    (net (code "22") (name "Net-(C11-Pad2)") (class "Default")
      (node (ref "C11") (pin "2") (pinfunction "2_2") (pintype "passive"))
      (node (ref "R25") (pin "2") (pinfunction "2_2") (pintype "passive"))
    )
    (net (code "23") (name "Net-(C12-Pad1)") (class "Default")
      (node (ref "C12") (pin "1") (pinfunction "1_1") (pintype "passive"))
      (node (ref "TP5") (pin "1") (pinfunction "1_1") (pintype "passive"))
    )
    (net (code "24") (name "Net-(C12-Pad2)") (class "Default")
      (node (ref "C12") (pin "2") (pinfunction "2_2") (pintype "passive"))
      (node (ref "R27") (pin "2") (pinfunction "2_2") (pintype "passive"))
    )
    (net (code "25") (name "Net-(C13-Pad1)") (class "Default")
      (node (ref "C13") (pin "1") (pinfunction "1_1") (pintype "passive"))
      (node (ref "R31") (pin "2") (pinfunction "2_2") (pintype "passive"))
      (node (ref "TP6") (pin "1") (pinfunction "1_1") (pintype "passive"))
    )
    (net (code "26") (name "Net-(D1-K)") (class "Default")
      (node (ref "D1") (pin "1") (pinfunction "K_1") (pintype "passive"))
      (node (ref "R5") (pin "1") (pinfunction "1_1") (pintype "passive"))
    )
    (net (code "27") (name "Net-(D2-A)") (class "Default")
      (node (ref "D2") (pin "1") (pinfunction "A_1") (pintype "passive"))
      (node (ref "R12") (pin "2") (pinfunction "2_2") (pintype "passive"))
    )
    (net (code "28") (name "Net-(D2-K)") (class "Default")
      (node (ref "D2") (pin "2") (pinfunction "K_2") (pintype "passive"))
      (node (ref "D3") (pin "2") (pinfunction "K_2") (pintype "passive"))
      (node (ref "R18") (pin "2") (pinfunction "2_2") (pintype "passive"))
    )
    (net (code "29") (name "Net-(D3-A)") (class "Default")
      (node (ref "D3") (pin "1") (pinfunction "A_1") (pintype "passive"))
      (node (ref "R17") (pin "2") (pinfunction "2_2") (pintype "passive"))
      (node (ref "R21") (pin "2") (pinfunction "2_2") (pintype "passive"))
    )
    (net (code "30") (name "Net-(D4-B_C)") (class "Default")
      (node (ref "D4") (pin "2") (pinfunction "B_C_2") (pintype "passive"))
      (node (ref "R24") (pin "2") (pinfunction "2_2") (pintype "passive"))
    )
    (net (code "31") (name "Net-(D4-G_C)") (class "Default")
      (node (ref "D4") (pin "1") (pinfunction "G_C_1") (pintype "passive"))
      (node (ref "R23") (pin "2") (pinfunction "2_2") (pintype "passive"))
    )
    (net (code "32") (name "Net-(D4-R_C)") (class "Default")
      (node (ref "D4") (pin "4") (pinfunction "R_C_4") (pintype "passive"))
      (node (ref "R22") (pin "2") (pinfunction "2_2") (pintype "passive"))
    )
    (net (code "33") (name "Net-(IC1-PB3)") (class "Default")
      (node (ref "IC1") (pin "23") (pinfunction "PB3_23") (pintype "passive"))
      (node (ref "R1") (pin "1") (pinfunction "1_1") (pintype "passive"))
    )
    (net (code "34") (name "Net-(IC2-PA0{slash}~{RESET}{slash}UPDI)") (class "Default")
      (node (ref "IC2") (pin "23") (pinfunction "PA0/~{RESET}/UPDI_23") (pintype "passive"))
      (node (ref "R2") (pin "2") (pinfunction "2_2") (pintype "passive"))
      (node (ref "R6") (pin "2") (pinfunction "2_2") (pintype "passive"))
    )
    (net (code "35") (name "Net-(IC2-PA2)") (class "Default")
      (node (ref "IC2") (pin "1") (pinfunction "PA2_1") (pintype "passive"))
      (node (ref "R7") (pin "1") (pinfunction "1_1") (pintype "passive"))
    )
    (net (code "36") (name "Net-(IC2-PB2{slash}TOSC2)") (class "Default")
      (node (ref "IC2") (pin "14") (pinfunction "PB2/TOSC2_14") (pintype "passive"))
      (node (ref "R15") (pin "1") (pinfunction "1_1") (pintype "passive"))
    )
    (net (code "37") (name "Net-(IC2-PB3{slash}TOSC1)") (class "Default")
      (node (ref "IC2") (pin "13") (pinfunction "PB3/TOSC1_13") (pintype "passive"))
      (node (ref "R16") (pin "1") (pinfunction "1_1") (pintype "passive"))
    )
    (net (code "38") (name "Net-(IC2-PC5)") (class "Default")
      (node (ref "IC2") (pin "22") (pinfunction "PC5_22") (pintype "passive"))
      (node (ref "R20") (pin "1") (pinfunction "1_1") (pintype "passive"))
    )
    (net (code "39") (name "Net-(J1-CC1)") (class "Default")
      (node (ref "J1") (pin "A5") (pinfunction "CC1_A5") (pintype "bidirectional"))
      (node (ref "R32") (pin "1") (pinfunction "1_1") (pintype "passive"))
    )
    (net (code "40") (name "Net-(Q1-B)") (class "Default")
      (node (ref "Q1") (pin "1") (pinfunction "B_1") (pintype "passive"))
      (node (ref "R11") (pin "1") (pinfunction "1_1") (pintype "passive"))
      (node (ref "R8") (pin "2") (pinfunction "2_2") (pintype "passive"))
    )
    (net (code "41") (name "Net-(Q1-C)") (class "Default")
      (node (ref "C4") (pin "1") (pinfunction "1_1") (pintype "passive"))
      (node (ref "Q1") (pin "2") (pinfunction "C_2") (pintype "passive"))
      (node (ref "R3") (pin "2") (pinfunction "2_2") (pintype "passive"))
      (node (ref "R4") (pin "2") (pinfunction "2_2") (pintype "passive"))
    )
    (net (code "42") (name "Net-(Q2-G)") (class "Default")
      (node (ref "Q2") (pin "3") (pinfunction "G_3") (pintype "passive"))
      (node (ref "R10") (pin "2") (pinfunction "2_2") (pintype "passive"))
      (node (ref "R14") (pin "1") (pinfunction "1_1") (pintype "passive"))
    )
    (net (code "43") (name "Net-(Q3-B)") (class "Default")
      (node (ref "C10") (pin "1") (pinfunction "1_1") (pintype "passive"))
      (node (ref "Q3") (pin "1") (pinfunction "B_1") (pintype "passive"))
      (node (ref "R18") (pin "1") (pinfunction "1_1") (pintype "passive"))
      (node (ref "R19") (pin "2") (pinfunction "2_2") (pintype "passive"))
    )
    (net (code "44") (name "Net-(Q3-C)") (class "Default")
      (node (ref "Q3") (pin "2") (pinfunction "C_2") (pintype "passive"))
      (node (ref "R14") (pin "2") (pinfunction "2_2") (pintype "passive"))
    )
    (net (code "45") (name "Net-(R12-Pad1)") (class "Default")
      (node (ref "R12") (pin "1") (pinfunction "1_1") (pintype "passive"))
      (node (ref "R8") (pin "1") (pinfunction "1_1") (pintype "passive"))
      (node (ref "S1") (pin "1") (pinfunction "1_1") (pintype "passive"))
    )
    (net (code "46") (name "Net-(U1-SW)") (class "Default")
      (node (ref "L1") (pin "1") (pinfunction "1_1") (pintype "passive"))
      (node (ref "U1") (pin "5") (pinfunction "SW_5") (pintype "passive"))
    )
    (net (code "47") (name "Net-(U2-TXD)") (class "Default")
      (node (ref "R5") (pin "2") (pinfunction "2_2") (pintype "passive"))
      (node (ref "U2") (pin "6") (pinfunction "TXD_6") (pintype "passive"))
    )
    (net (code "48") (name "Net-(U2-V3)") (class "Default")
      (node (ref "C8") (pin "1") (pinfunction "1_1") (pintype "passive"))
      (node (ref "U2") (pin "8") (pinfunction "V3_8") (pintype "passive"))
    )
    (net (code "49") (name "Net-(U3-FB)") (class "Default")
      (node (ref "R30") (pin "2") (pinfunction "2_2") (pintype "passive"))
      (node (ref "R33") (pin "1") (pinfunction "1_1") (pintype "passive"))
      (node (ref "U3") (pin "8") (pinfunction "FB_8") (pintype "input"))
    )
    (net (code "50") (name "Net-(U3-ISET)") (class "Default")
      (node (ref "R34") (pin "1") (pinfunction "1_1") (pintype "passive"))
      (node (ref "U3") (pin "2") (pinfunction "ISET_2") (pintype "bidirectional"))
    )
    (net (code "51") (name "Net-(U3-RC)") (class "Default")
      (node (ref "C16") (pin "2") (pinfunction "2_2") (pintype "passive"))
      (node (ref "R29") (pin "2") (pinfunction "2_2") (pintype "passive"))
      (node (ref "U3") (pin "6") (pinfunction "RC_6") (pintype "passive"))
    )
    (net (code "52") (name "VBUS") (class "Default")
      (node (ref "J1") (pin "A4_B9") (pinfunction "VBUS_A4_B9") (pintype "power_in"))
      (node (ref "J1") (pin "B4_A9") (pinfunction "VBUS_B4_A9") (pintype "power_in"))
      (node (ref "R26") (pin "1") (pinfunction "1_1") (pintype "passive"))
    )
    (net (code "53") (name "VBUS_IN") (class "Default")
      (node (ref "C14") (pin "2") (pinfunction "2_2") (pintype "passive"))
      (node (ref "R20") (pin "2") (pinfunction "2_2") (pintype "passive"))
      (node (ref "R26") (pin "2") (pinfunction "2_2") (pintype "passive"))
      (node (ref "R28") (pin "1") (pinfunction "1_1") (pintype "passive"))
      (node (ref "R29") (pin "1") (pinfunction "1_1") (pintype "passive"))
      (node (ref "U3") (pin "4") (pinfunction "VIN_4") (pintype "power_in"))
    )
    (net (code "54") (name "VOUT") (class "Default")
      (node (ref "C1") (pin "2") (pinfunction "2_2") (pintype "passive"))
      (node (ref "L1") (pin "2") (pinfunction "2_2") (pintype "passive"))
      (node (ref "Q2") (pin "6") (pinfunction "D@4_6") (pintype "passive"))
      (node (ref "U1") (pin "1") (pinfunction "EN_1") (pintype "passive"))
      (node (ref "U1") (pin "8") (pinfunction "VIN_8") (pintype "passive"))
    )
    (net (code "55") (name "unconnected-(IC1-3V3-Pad6)") (class "Default")
      (node (ref "IC1") (pin "6") (pinfunction "3V3_6") (pintype "passive+no_connect"))
    )
    (net (code "56") (name "unconnected-(IC1-DM-Pad4)") (class "Default")
      (node (ref "IC1") (pin "4") (pinfunction "DM_4") (pintype "passive+no_connect"))
    )
    (net (code "57") (name "unconnected-(IC1-DP-Pad5)") (class "Default")
      (node (ref "IC1") (pin "5") (pinfunction "DP_5") (pintype "passive+no_connect"))
    )
    (net (code "58") (name "unconnected-(IC1-PA3-Pad1)") (class "Default")
      (node (ref "IC1") (pin "1") (pinfunction "PA3_1") (pintype "passive+no_connect"))
    )
    (net (code "59") (name "unconnected-(IC1-PA4-Pad2)") (class "Default")
      (node (ref "IC1") (pin "2") (pinfunction "PA4_2") (pintype "passive+no_connect"))
    )
    (net (code "60") (name "unconnected-(IC1-PA5-Pad3)") (class "Default")
      (node (ref "IC1") (pin "3") (pinfunction "PA5_3") (pintype "passive+no_connect"))
    )
    (net (code "61") (name "unconnected-(IC1-PB2-Pad24)") (class "Default")
      (node (ref "IC1") (pin "24") (pinfunction "PB2_24") (pintype "passive+no_connect"))
    )
    (net (code "62") (name "unconnected-(IC1-PB4-Pad22)") (class "Default")
      (node (ref "IC1") (pin "22") (pinfunction "PB4_22") (pintype "passive+no_connect"))
    )
    (net (code "63") (name "unconnected-(IC1-PB5-Pad21)") (class "Default")
      (node (ref "IC1") (pin "21") (pinfunction "PB5_21") (pintype "passive+no_connect"))
    )
    (net (code "64") (name "unconnected-(IC1-PB6-Pad20)") (class "Default")
      (node (ref "IC1") (pin "20") (pinfunction "PB6_20") (pintype "passive+no_connect"))
    )
    (net (code "65") (name "unconnected-(IC1-PC1-Pad14)") (class "Default")
      (node (ref "IC1") (pin "14") (pinfunction "PC1_14") (pintype "passive"))
    )
    (net (code "66") (name "unconnected-(IC1-PC3-Pad15)") (class "Default")
      (node (ref "IC1") (pin "15") (pinfunction "PC3_15") (pintype "passive+no_connect"))
    )
    (net (code "67") (name "unconnected-(IC1-PC4-Pad16)") (class "Default")
      (node (ref "IC1") (pin "16") (pinfunction "PC4_16") (pintype "passive+no_connect"))
    )
    (net (code "68") (name "unconnected-(IC1-PC5-Pad17)") (class "Default")
      (node (ref "IC1") (pin "17") (pinfunction "PC5_17") (pintype "passive+no_connect"))
    )
    (net (code "69") (name "unconnected-(IC1-PR1-Pad19)") (class "Default")
      (node (ref "IC1") (pin "19") (pinfunction "PR1_19") (pintype "passive+no_connect"))
    )
    (net (code "70") (name "unconnected-(IC1-PR2-Pad18)") (class "Default")
      (node (ref "IC1") (pin "18") (pinfunction "PR2_18") (pintype "passive+no_connect"))
    )
    (net (code "71") (name "unconnected-(IC2-EXTCLK_{slash}PA3-Pad2)") (class "Default")
      (node (ref "IC2") (pin "2") (pinfunction "EXTCLK_/PA3_2") (pintype "passive+no_connect"))
    )
    (net (code "72") (name "unconnected-(IC2-PA4-Pad5)") (class "Default")
      (node (ref "IC2") (pin "5") (pinfunction "PA4_5") (pintype "passive"))
    )
    (net (code "73") (name "unconnected-(IC2-PA5-Pad6)") (class "Default")
      (node (ref "IC2") (pin "6") (pinfunction "PA5_6") (pintype "passive"))
    )
    (net (code "74") (name "unconnected-(IC2-PA6-Pad7)") (class "Default")
      (node (ref "IC2") (pin "7") (pinfunction "PA6_7") (pintype "passive+no_connect"))
    )
    (net (code "75") (name "unconnected-(IC2-PA7-Pad8)") (class "Default")
      (node (ref "IC2") (pin "8") (pinfunction "PA7_8") (pintype "passive+no_connect"))
    )
    (net (code "76") (name "unconnected-(IC2-PB1-Pad15)") (class "Default")
      (node (ref "IC2") (pin "15") (pinfunction "PB1_15") (pintype "passive"))
    )
    (net (code "77") (name "unconnected-(IC2-PB4-Pad12)") (class "Default")
      (node (ref "IC2") (pin "12") (pinfunction "PB4_12") (pintype "passive"))
    )
    (net (code "78") (name "unconnected-(IC2-PB5-Pad11)") (class "Default")
      (node (ref "IC2") (pin "11") (pinfunction "PB5_11") (pintype "passive"))
    )
    (net (code "79") (name "unconnected-(IC2-PB6-Pad10)") (class "Default")
      (node (ref "IC2") (pin "10") (pinfunction "PB6_10") (pintype "passive+no_connect"))
    )
    (net (code "80") (name "unconnected-(IC2-PB7-Pad9)") (class "Default")
      (node (ref "IC2") (pin "9") (pinfunction "PB7_9") (pintype "passive+no_connect"))
    )
    (net (code "81") (name "unconnected-(J1-CC2-PadB5)") (class "Default")
      (node (ref "J1") (pin "B5") (pinfunction "CC2_B5") (pintype "bidirectional+no_connect"))
    )
    (net (code "82") (name "unconnected-(J1-DN1-PadA7)") (class "Default")
      (node (ref "J1") (pin "A7") (pinfunction "DN1_A7") (pintype "bidirectional+no_connect"))
    )
    (net (code "83") (name "unconnected-(J1-DP1-PadA6)") (class "Default")
      (node (ref "J1") (pin "A6") (pinfunction "DP1_A6") (pintype "bidirectional+no_connect"))
    )
    (net (code "84") (name "unconnected-(J1-SBU1-PadA8)") (class "Default")
      (node (ref "J1") (pin "A8") (pinfunction "SBU1_A8") (pintype "bidirectional+no_connect"))
    )
    (net (code "85") (name "unconnected-(J1-SBU2-PadB8)") (class "Default")
      (node (ref "J1") (pin "B8") (pinfunction "SBU2_B8") (pintype "bidirectional+no_connect"))
    )
    (net (code "86") (name "unconnected-(Q2-D@1-Pad1)") (class "Default")
      (node (ref "Q2") (pin "1") (pinfunction "D@1_1") (pintype "passive"))
    )
    (net (code "87") (name "unconnected-(Q2-D@2-Pad2)") (class "Default")
      (node (ref "Q2") (pin "2") (pinfunction "D@2_2") (pintype "passive"))
    )
    (net (code "88") (name "unconnected-(Q2-D@3-Pad5)") (class "Default")
      (node (ref "Q2") (pin "5") (pinfunction "D@3_5") (pintype "passive"))
    )
    (net (code "89") (name "unconnected-(U1-NC-Pad2)") (class "Default")
      (node (ref "U1") (pin "2") (pinfunction "NC_2") (pintype "passive+no_connect"))
    )
    (net (code "90") (name "unconnected-(U1-PG-Pad3)") (class "Default")
      (node (ref "U1") (pin "3") (pinfunction "PG_3") (pintype "passive+no_connect"))
    )
    (net (code "91") (name "unconnected-(U2-RTS#-Pad4)") (class "Default")
      (node (ref "U2") (pin "4") (pinfunction "RTS#_4") (pintype "passive+no_connect"))
    )
  )
)
